# TREM_STM_DAUGHTERBOARD.net
KiCad netlist of a schematic drawn in EAGLE
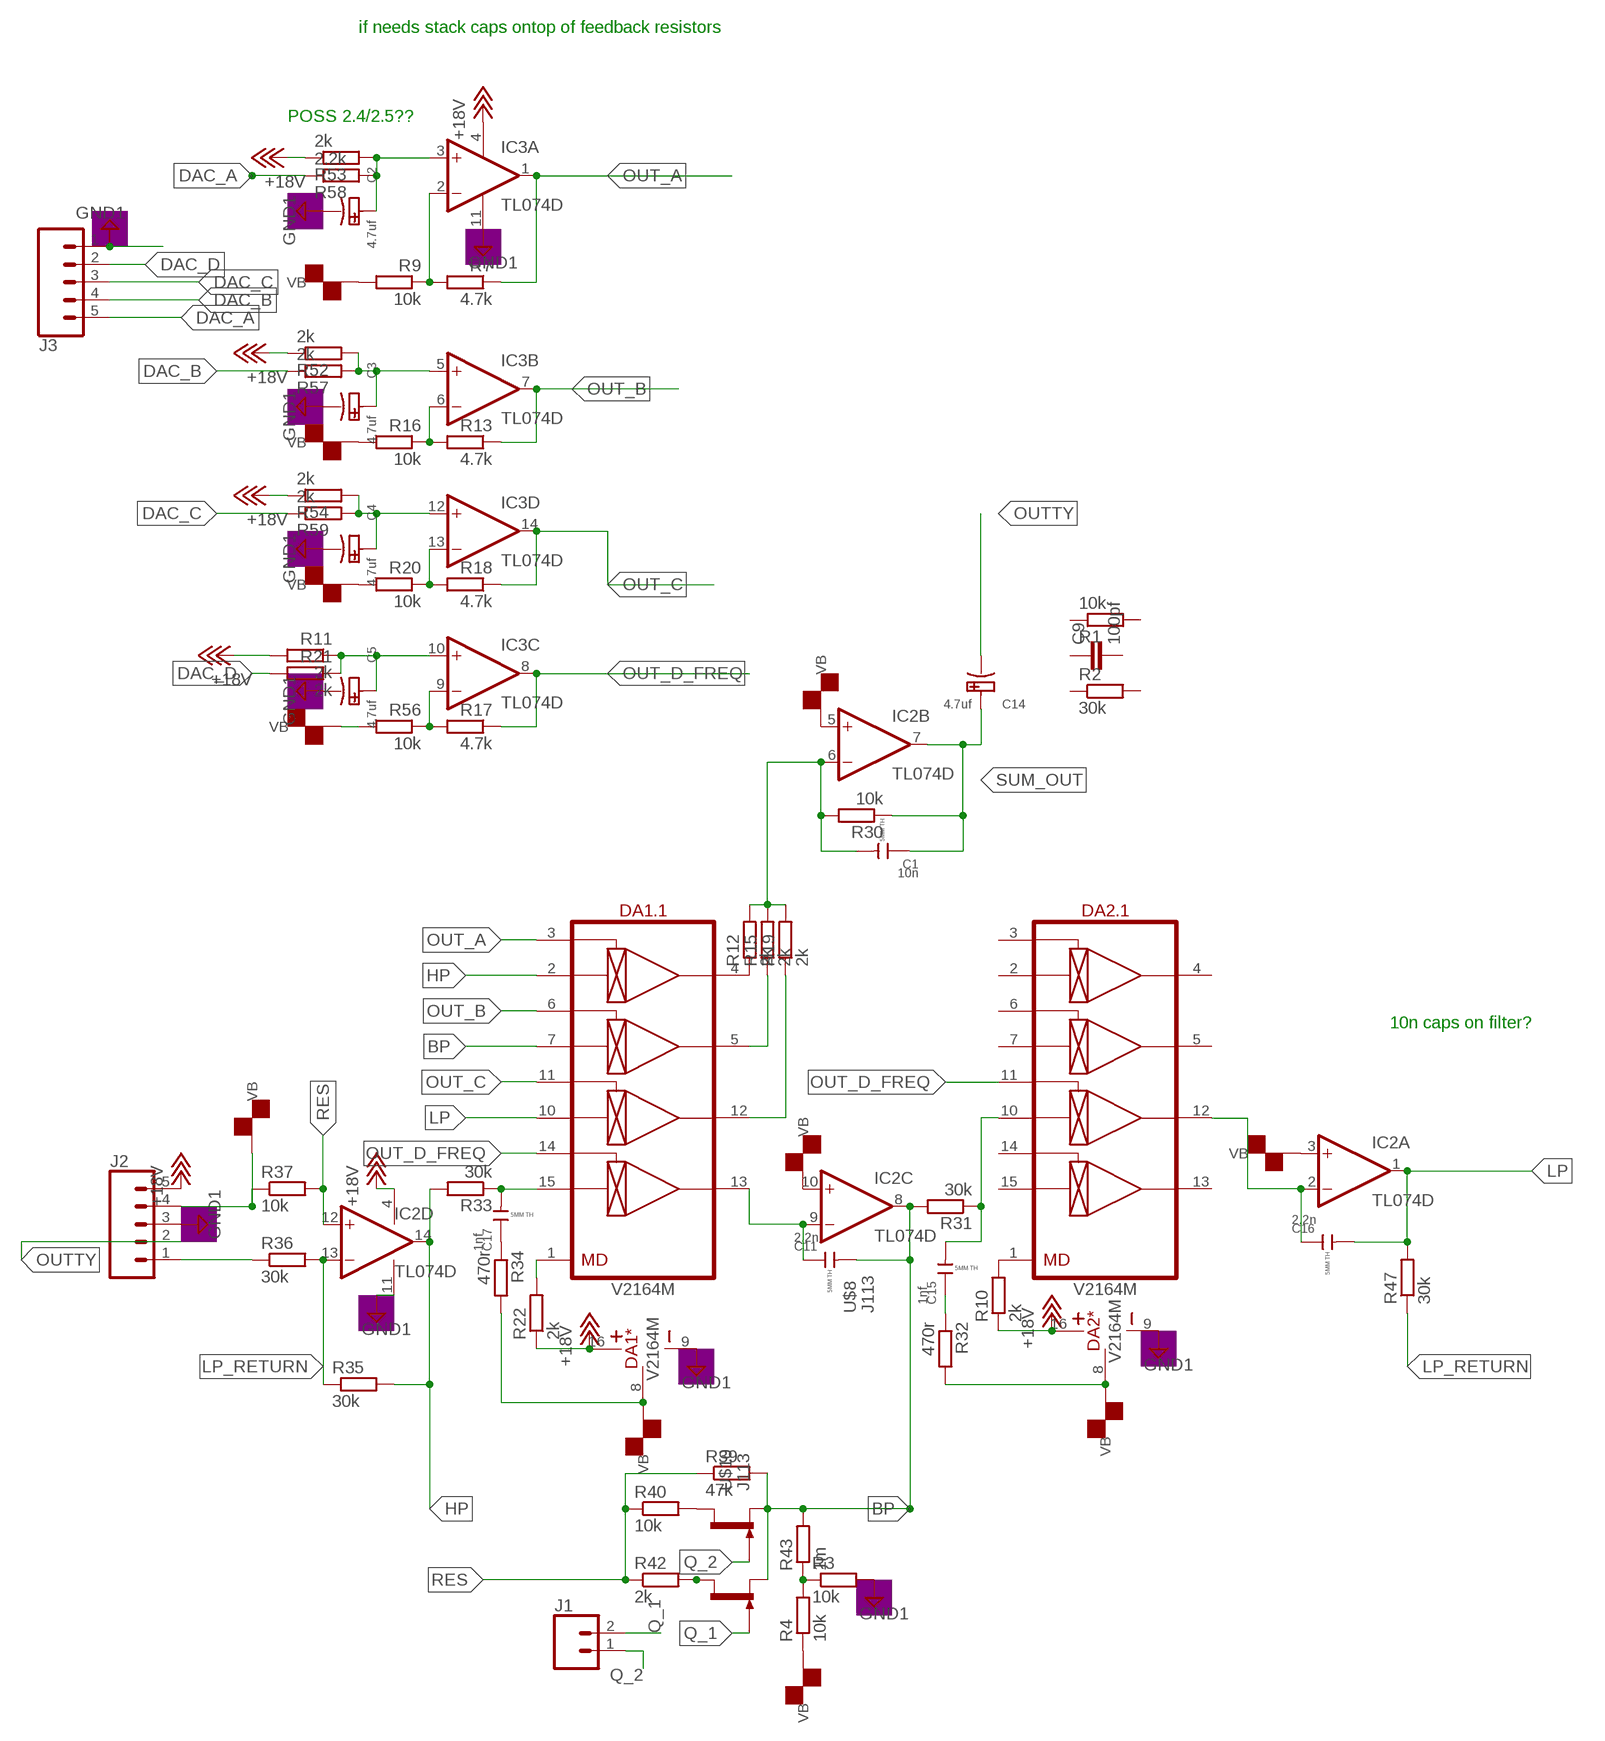
[diagram p0: schematic, sheet 1]

(export (version "E")
  (design (tool "Eeschema 10.0.6"))
  (components
    (comp (ref "C1")
      (value "10n")
      (footprint "eagle-import:CERAMIC-5MM")
      (fields (field (name "PACKAGE") "5MM TH"))
      (libsource (lib "eagle-import") (part "THRU_HOLE_5MM_SPACING"))
    )
    (comp (ref "C2")
      (value "4.7uf")
      (footprint "eagle-import:PC-D5.3MM")
      (libsource (lib "eagle-import") (part "THRU-HOLE-POLARIZED"))
    )
    (comp (ref "C3")
      (value "4.7uf")
      (footprint "eagle-import:PC-D5.3MM")
      (libsource (lib "eagle-import") (part "THRU-HOLE-POLARIZED"))
    )
    (comp (ref "C4")
      (value "4.7uf")
      (footprint "eagle-import:PC-D5.3MM")
      (libsource (lib "eagle-import") (part "THRU-HOLE-POLARIZED"))
    )
    (comp (ref "C5")
      (value "4.7uf")
      (footprint "eagle-import:PC-D5.3MM")
      (libsource (lib "eagle-import") (part "THRU-HOLE-POLARIZED"))
    )
    (comp (ref "C9")
      (value "100pf")
      (footprint "eagle-import:C1206")
      (libsource (lib "eagle-import") (part "C-EUC1206"))
    )
    (comp (ref "C11")
      (value "2.2n")
      (footprint "eagle-import:CERAMIC-5MM")
      (fields (field (name "PACKAGE") "5MM TH"))
      (libsource (lib "eagle-import") (part "THRU_HOLE_5MM_SPACING"))
    )
    (comp (ref "C14")
      (value "4.7uf")
      (footprint "eagle-import:PC-D5.3MM")
      (libsource (lib "eagle-import") (part "THRU-HOLE-POLARIZED"))
    )
    (comp (ref "C15")
      (value "1nf")
      (footprint "eagle-import:CERAMIC-5MM")
      (fields (field (name "PACKAGE") "5MM TH"))
      (libsource (lib "eagle-import") (part "THRU_HOLE_5MM_SPACING"))
    )
    (comp (ref "C16")
      (value "2.2n")
      (footprint "eagle-import:CERAMIC-5MM")
      (fields (field (name "PACKAGE") "5MM TH"))
      (libsource (lib "eagle-import") (part "THRU_HOLE_5MM_SPACING"))
    )
    (comp (ref "C17")
      (value "1nf")
      (footprint "eagle-import:CERAMIC-5MM")
      (fields (field (name "PACKAGE") "5MM TH"))
      (libsource (lib "eagle-import") (part "THRU_HOLE_5MM_SPACING"))
    )
    (comp (ref "DA1")
      (value "V2164M")
      (footprint "eagle-import:SO-16")
      (libsource (lib "eagle-import") (part "V2164M"))
    )
    (comp (ref "DA2")
      (value "V2164M")
      (footprint "eagle-import:SO-16")
      (libsource (lib "eagle-import") (part "V2164M"))
    )
    (comp (ref "IC2")
      (value "TL074D")
      (footprint "eagle-import:SO14")
      (libsource (lib "eagle-import") (part "TL074D"))
    )
    (comp (ref "IC3")
      (value "TL074D")
      (footprint "eagle-import:SO14")
      (libsource (lib "eagle-import") (part "TL074D"))
    )
    (comp (ref "J1")
      (value "CONN_02PTH3")
      (footprint "eagle-import:1X02_LONGPADS")
      (libsource (lib "eagle-import") (part "CONN_02PTH3"))
    )
    (comp (ref "J2")
      (value "CONN_05PTH_LONGPADS")
      (footprint "eagle-import:1X05_LONGPADS")
      (libsource (lib "eagle-import") (part "CONN_05PTH_LONGPADS"))
    )
    (comp (ref "J3")
      (value "CONN_05PTH_LONGPADS")
      (footprint "eagle-import:1X05_LONGPADS")
      (libsource (lib "eagle-import") (part "CONN_05PTH_LONGPADS"))
    )
    (comp (ref "R1")
      (value "10k")
      (footprint "eagle-import:M1206")
      (libsource (lib "eagle-import") (part "R-EU_M1206"))
    )
    (comp (ref "R2")
      (value "30k")
      (footprint "eagle-import:M1206")
      (libsource (lib "eagle-import") (part "R-EU_M1206"))
    )
    (comp (ref "R3")
      (value "10k")
      (footprint "eagle-import:M1206")
      (libsource (lib "eagle-import") (part "R-EU_M1206"))
    )
    (comp (ref "R4")
      (value "10k")
      (footprint "eagle-import:M1206")
      (libsource (lib "eagle-import") (part "R-EU_M1206"))
    )
    (comp (ref "R7")
      (value "4.7k")
      (footprint "eagle-import:M1206")
      (libsource (lib "eagle-import") (part "R-EU_M1206"))
    )
    (comp (ref "R9")
      (value "10k")
      (footprint "eagle-import:M1206")
      (libsource (lib "eagle-import") (part "R-EU_M1206"))
    )
    (comp (ref "R10")
      (value "2k")
      (footprint "eagle-import:M1206")
      (libsource (lib "eagle-import") (part "R-EU_M1206"))
    )
    (comp (ref "R11")
      (value "2k")
      (footprint "eagle-import:M1206")
      (libsource (lib "eagle-import") (part "R-EU_M1206"))
    )
    (comp (ref "R12")
      (value "2k")
      (footprint "eagle-import:M1206")
      (libsource (lib "eagle-import") (part "R-EU_M1206"))
    )
    (comp (ref "R13")
      (value "4.7k")
      (footprint "eagle-import:M1206")
      (libsource (lib "eagle-import") (part "R-EU_M1206"))
    )
    (comp (ref "R15")
      (value "2k")
      (footprint "eagle-import:M1206")
      (libsource (lib "eagle-import") (part "R-EU_M1206"))
    )
    (comp (ref "R16")
      (value "10k")
      (footprint "eagle-import:M1206")
      (libsource (lib "eagle-import") (part "R-EU_M1206"))
    )
    (comp (ref "R17")
      (value "4.7k")
      (footprint "eagle-import:M1206")
      (libsource (lib "eagle-import") (part "R-EU_M1206"))
    )
    (comp (ref "R18")
      (value "4.7k")
      (footprint "eagle-import:M1206")
      (libsource (lib "eagle-import") (part "R-EU_M1206"))
    )
    (comp (ref "R19")
      (value "2k")
      (footprint "eagle-import:M1206")
      (libsource (lib "eagle-import") (part "R-EU_M1206"))
    )
    (comp (ref "R20")
      (value "10k")
      (footprint "eagle-import:M1206")
      (libsource (lib "eagle-import") (part "R-EU_M1206"))
    )
    (comp (ref "R21")
      (value "2k")
      (footprint "eagle-import:M1206")
      (libsource (lib "eagle-import") (part "R-EU_M1206"))
    )
    (comp (ref "R22")
      (value "2k")
      (footprint "eagle-import:M1206")
      (libsource (lib "eagle-import") (part "R-EU_M1206"))
    )
    (comp (ref "R30")
      (value "10k")
      (footprint "eagle-import:M1206")
      (libsource (lib "eagle-import") (part "R-EU_M1206"))
    )
    (comp (ref "R31")
      (value "30k")
      (footprint "eagle-import:M1206")
      (libsource (lib "eagle-import") (part "R-EU_M1206"))
    )
    (comp (ref "R32")
      (value "470r")
      (footprint "eagle-import:M1206")
      (libsource (lib "eagle-import") (part "R-EU_M1206"))
    )
    (comp (ref "R33")
      (value "30k")
      (footprint "eagle-import:M1206")
      (libsource (lib "eagle-import") (part "R-EU_M1206"))
    )
    (comp (ref "R34")
      (value "470r")
      (footprint "eagle-import:M1206")
      (libsource (lib "eagle-import") (part "R-EU_M1206"))
    )
    (comp (ref "R35")
      (value "30k")
      (footprint "eagle-import:M1206")
      (libsource (lib "eagle-import") (part "R-EU_M1206"))
    )
    (comp (ref "R36")
      (value "30k")
      (footprint "eagle-import:M1206")
      (libsource (lib "eagle-import") (part "R-EU_M1206"))
    )
    (comp (ref "R37")
      (value "10k")
      (footprint "eagle-import:M1206")
      (libsource (lib "eagle-import") (part "R-EU_M1206"))
    )
    (comp (ref "R39")
      (value "47k")
      (footprint "eagle-import:M1206")
      (libsource (lib "eagle-import") (part "R-EU_M1206"))
    )
    (comp (ref "R40")
      (value "10k")
      (footprint "eagle-import:M1206")
      (libsource (lib "eagle-import") (part "R-EU_M1206"))
    )
    (comp (ref "R42")
      (value "2k")
      (footprint "eagle-import:M1206")
      (libsource (lib "eagle-import") (part "R-EU_M1206"))
    )
    (comp (ref "R43")
      (value "1m")
      (footprint "eagle-import:M1206")
      (libsource (lib "eagle-import") (part "R-EU_M1206"))
    )
    (comp (ref "R47")
      (value "30k")
      (footprint "eagle-import:M1206")
      (libsource (lib "eagle-import") (part "R-EU_M1206"))
    )
    (comp (ref "R52")
      (value "2k")
      (footprint "eagle-import:M1206")
      (libsource (lib "eagle-import") (part "R-EU_M1206"))
    )
    (comp (ref "R53")
      (value "2k")
      (footprint "eagle-import:M1206")
      (libsource (lib "eagle-import") (part "R-EU_M1206"))
    )
    (comp (ref "R54")
      (value "2k")
      (footprint "eagle-import:M1206")
      (libsource (lib "eagle-import") (part "R-EU_M1206"))
    )
    (comp (ref "R56")
      (value "10k")
      (footprint "eagle-import:M1206")
      (libsource (lib "eagle-import") (part "R-EU_M1206"))
    )
    (comp (ref "R57")
      (value "2k")
      (footprint "eagle-import:M1206")
      (libsource (lib "eagle-import") (part "R-EU_M1206"))
    )
    (comp (ref "R58")
      (value "2.2k")
      (footprint "eagle-import:M1206")
      (libsource (lib "eagle-import") (part "R-EU_M1206"))
    )
    (comp (ref "R59")
      (value "2k")
      (footprint "eagle-import:M1206")
      (libsource (lib "eagle-import") (part "R-EU_M1206"))
    )
    (comp (ref "U$8")
      (value "J113")
      (footprint "eagle-import:TO92-")
      (libsource (lib "eagle-import") (part "J111"))
    )
    (comp (ref "U$10")
      (value "J113")
      (footprint "eagle-import:TO92-")
      (libsource (lib "eagle-import") (part "J111"))
    )
  )
  (nets
    (net (code "1") (name "+18V") (class "Default")
      (node (ref "DA1") (pin "16") (pinfunction "V+_16") (pintype "power_in"))
      (node (ref "DA2") (pin "16") (pinfunction "V+_16") (pintype "power_in"))
      (node (ref "IC2") (pin "4") (pinfunction "V+_4") (pintype "power_in"))
      (node (ref "IC3") (pin "4") (pinfunction "V+_4") (pintype "power_in"))
      (node (ref "J2") (pin "5") (pinfunction "5_5") (pintype "passive"))
      (node (ref "R10") (pin "1") (pinfunction "1_1") (pintype "passive"))
      (node (ref "R11") (pin "2") (pinfunction "2_2") (pintype "passive"))
      (node (ref "R22") (pin "1") (pinfunction "1_1") (pintype "passive"))
      (node (ref "R52") (pin "1") (pinfunction "1_1") (pintype "passive"))
      (node (ref "R53") (pin "1") (pinfunction "1_1") (pintype "passive"))
      (node (ref "R54") (pin "1") (pinfunction "1_1") (pintype "passive"))
    )
    (net (code "2") (name "BP") (class "Default")
      (node (ref "C11") (pin "2") (pinfunction "2_2") (pintype "passive"))
      (node (ref "DA1") (pin "7") (pinfunction "IN2_7") (pintype "input"))
      (node (ref "IC2") (pin "8") (pinfunction "OUT_8") (pintype "output"))
      (node (ref "R31") (pin "2") (pinfunction "2_2") (pintype "passive"))
      (node (ref "R39") (pin "2") (pinfunction "2_2") (pintype "passive"))
      (node (ref "R43") (pin "2") (pinfunction "2_2") (pintype "passive"))
      (node (ref "U$10") (pin "2") (pinfunction "S_2") (pintype "passive"))
      (node (ref "U$8") (pin "2") (pinfunction "S_2") (pintype "passive"))
    )
    (net (code "3") (name "DAC_A") (class "Default")
      (node (ref "J3") (pin "5") (pinfunction "5_5") (pintype "passive"))
      (node (ref "R58") (pin "1") (pinfunction "1_1") (pintype "passive"))
    )
    (net (code "4") (name "DAC_B") (class "Default")
      (node (ref "J3") (pin "4") (pinfunction "4_4") (pintype "passive"))
      (node (ref "R57") (pin "1") (pinfunction "1_1") (pintype "passive"))
    )
    (net (code "5") (name "DAC_C") (class "Default")
      (node (ref "J3") (pin "3") (pinfunction "3_3") (pintype "passive"))
      (node (ref "R59") (pin "1") (pinfunction "1_1") (pintype "passive"))
    )
    (net (code "6") (name "DAC_D") (class "Default")
      (node (ref "J3") (pin "2") (pinfunction "2_2") (pintype "passive"))
      (node (ref "R21") (pin "2") (pinfunction "2_2") (pintype "passive"))
    )
    (net (code "7") (name "GND1") (class "Default")
      (node (ref "C2") (pin "-") (pinfunction "-_-") (pintype "passive"))
      (node (ref "C3") (pin "-") (pinfunction "-_-") (pintype "passive"))
      (node (ref "C4") (pin "-") (pinfunction "-_-") (pintype "passive"))
      (node (ref "C5") (pin "-") (pinfunction "-_-") (pintype "passive"))
      (node (ref "DA1") (pin "9") (pinfunction "V-_9") (pintype "power_in"))
      (node (ref "DA2") (pin "9") (pinfunction "V-_9") (pintype "power_in"))
      (node (ref "IC2") (pin "11") (pinfunction "V-_11") (pintype "power_in"))
      (node (ref "IC3") (pin "11") (pinfunction "V-_11") (pintype "power_in"))
      (node (ref "J2") (pin "3") (pinfunction "3_3") (pintype "passive"))
      (node (ref "J3") (pin "1") (pinfunction "1_1") (pintype "passive"))
      (node (ref "R3") (pin "2") (pinfunction "2_2") (pintype "passive"))
    )
    (net (code "8") (name "HP") (class "Default")
      (node (ref "DA1") (pin "2") (pinfunction "IN1_2") (pintype "input"))
      (node (ref "IC2") (pin "14") (pinfunction "OUT_14") (pintype "output"))
      (node (ref "R33") (pin "2") (pinfunction "2_2") (pintype "passive"))
      (node (ref "R35") (pin "2") (pinfunction "2_2") (pintype "passive"))
    )
    (net (code "9") (name "LP") (class "Default")
      (node (ref "C16") (pin "2") (pinfunction "2_2") (pintype "passive"))
      (node (ref "DA1") (pin "10") (pinfunction "IN3_10") (pintype "input"))
      (node (ref "IC2") (pin "1") (pinfunction "OUT_1") (pintype "output"))
      (node (ref "R47") (pin "2") (pinfunction "2_2") (pintype "passive"))
    )
    (net (code "10") (name "LP_RETURN") (class "Default")
      (node (ref "IC2") (pin "13") (pinfunction "-IN_13") (pintype "input"))
      (node (ref "R35") (pin "1") (pinfunction "1_1") (pintype "passive"))
      (node (ref "R36") (pin "2") (pinfunction "2_2") (pintype "passive"))
      (node (ref "R47") (pin "1") (pinfunction "1_1") (pintype "passive"))
    )
    (net (code "11") (name "Net-(C15-Pad1)") (class "Default")
      (node (ref "C15") (pin "1") (pinfunction "1_1") (pintype "passive"))
      (node (ref "R32") (pin "1") (pinfunction "1_1") (pintype "passive"))
    )
    (net (code "12") (name "Net-(C17-Pad1)") (class "Default")
      (node (ref "C17") (pin "1") (pinfunction "1_1") (pintype "passive"))
      (node (ref "R34") (pin "1") (pinfunction "1_1") (pintype "passive"))
    )
    (net (code "13") (name "Net-(DA1B-IN4)") (class "Default")
      (node (ref "C17") (pin "2") (pinfunction "2_2") (pintype "passive"))
      (node (ref "DA1") (pin "15") (pinfunction "IN4_15") (pintype "input"))
      (node (ref "R33") (pin "1") (pinfunction "1_1") (pintype "passive"))
    )
    (net (code "14") (name "Net-(DA1B-MD)") (class "Default")
      (node (ref "DA1") (pin "1") (pinfunction "MD_1") (pintype "output"))
      (node (ref "R22") (pin "2") (pinfunction "2_2") (pintype "passive"))
    )
    (net (code "15") (name "Net-(DA1B-OUT1)") (class "Default")
      (node (ref "DA1") (pin "4") (pinfunction "OUT1_4") (pintype "output"))
      (node (ref "R12") (pin "1") (pinfunction "1_1") (pintype "passive"))
    )
    (net (code "16") (name "Net-(DA1B-OUT2)") (class "Default")
      (node (ref "DA1") (pin "5") (pinfunction "OUT2_5") (pintype "output"))
      (node (ref "R15") (pin "1") (pinfunction "1_1") (pintype "passive"))
    )
    (net (code "17") (name "Net-(DA1B-OUT3)") (class "Default")
      (node (ref "DA1") (pin "12") (pinfunction "OUT3_12") (pintype "output"))
      (node (ref "R19") (pin "1") (pinfunction "1_1") (pintype "passive"))
    )
    (net (code "18") (name "Net-(DA1B-OUT4)") (class "Default")
      (node (ref "C11") (pin "1") (pinfunction "1_1") (pintype "passive"))
      (node (ref "DA1") (pin "13") (pinfunction "OUT4_13") (pintype "output"))
      (node (ref "IC2") (pin "9") (pinfunction "-IN_9") (pintype "input"))
    )
    (net (code "19") (name "Net-(DA2B-IN3)") (class "Default")
      (node (ref "C15") (pin "2") (pinfunction "2_2") (pintype "passive"))
      (node (ref "DA2") (pin "10") (pinfunction "IN3_10") (pintype "input"))
      (node (ref "R31") (pin "1") (pinfunction "1_1") (pintype "passive"))
    )
    (net (code "20") (name "Net-(DA2B-MD)") (class "Default")
      (node (ref "DA2") (pin "1") (pinfunction "MD_1") (pintype "output"))
      (node (ref "R10") (pin "2") (pinfunction "2_2") (pintype "passive"))
    )
    (net (code "21") (name "Net-(DA2B-OUT3)") (class "Default")
      (node (ref "C16") (pin "1") (pinfunction "1_1") (pintype "passive"))
      (node (ref "DA2") (pin "12") (pinfunction "OUT3_12") (pintype "output"))
      (node (ref "IC2") (pin "2") (pinfunction "-IN_2") (pintype "input"))
    )
    (net (code "22") (name "Net-(IC2B--IN)") (class "Default")
      (node (ref "C1") (pin "2") (pinfunction "2_2") (pintype "passive"))
      (node (ref "IC2") (pin "6") (pinfunction "-IN_6") (pintype "input"))
      (node (ref "R12") (pin "2") (pinfunction "2_2") (pintype "passive"))
      (node (ref "R15") (pin "2") (pinfunction "2_2") (pintype "passive"))
      (node (ref "R19") (pin "2") (pinfunction "2_2") (pintype "passive"))
      (node (ref "R30") (pin "2") (pinfunction "2_2") (pintype "passive"))
    )
    (net (code "23") (name "Net-(IC3A-+IN)") (class "Default")
      (node (ref "C2") (pin "+") (pinfunction "+_+") (pintype "passive"))
      (node (ref "IC3") (pin "3") (pinfunction "+IN_3") (pintype "input"))
      (node (ref "R53") (pin "2") (pinfunction "2_2") (pintype "passive"))
      (node (ref "R58") (pin "2") (pinfunction "2_2") (pintype "passive"))
    )
    (net (code "24") (name "Net-(IC3A--IN)") (class "Default")
      (node (ref "IC3") (pin "2") (pinfunction "-IN_2") (pintype "input"))
      (node (ref "R7") (pin "2") (pinfunction "2_2") (pintype "passive"))
      (node (ref "R9") (pin "1") (pinfunction "1_1") (pintype "passive"))
    )
    (net (code "25") (name "Net-(IC3B-+IN)") (class "Default")
      (node (ref "C3") (pin "+") (pinfunction "+_+") (pintype "passive"))
      (node (ref "IC3") (pin "5") (pinfunction "+IN_5") (pintype "input"))
      (node (ref "R52") (pin "2") (pinfunction "2_2") (pintype "passive"))
      (node (ref "R57") (pin "2") (pinfunction "2_2") (pintype "passive"))
    )
    (net (code "26") (name "Net-(IC3B--IN)") (class "Default")
      (node (ref "IC3") (pin "6") (pinfunction "-IN_6") (pintype "input"))
      (node (ref "R13") (pin "2") (pinfunction "2_2") (pintype "passive"))
      (node (ref "R16") (pin "1") (pinfunction "1_1") (pintype "passive"))
    )
    (net (code "27") (name "Net-(IC3C-+IN)") (class "Default")
      (node (ref "C5") (pin "+") (pinfunction "+_+") (pintype "passive"))
      (node (ref "IC3") (pin "10") (pinfunction "+IN_10") (pintype "input"))
      (node (ref "R11") (pin "1") (pinfunction "1_1") (pintype "passive"))
      (node (ref "R21") (pin "1") (pinfunction "1_1") (pintype "passive"))
    )
    (net (code "28") (name "Net-(IC3C--IN)") (class "Default")
      (node (ref "IC3") (pin "9") (pinfunction "-IN_9") (pintype "input"))
      (node (ref "R17") (pin "2") (pinfunction "2_2") (pintype "passive"))
      (node (ref "R56") (pin "1") (pinfunction "1_1") (pintype "passive"))
    )
    (net (code "29") (name "Net-(IC3D-+IN)") (class "Default")
      (node (ref "C4") (pin "+") (pinfunction "+_+") (pintype "passive"))
      (node (ref "IC3") (pin "12") (pinfunction "+IN_12") (pintype "input"))
      (node (ref "R54") (pin "2") (pinfunction "2_2") (pintype "passive"))
      (node (ref "R59") (pin "2") (pinfunction "2_2") (pintype "passive"))
    )
    (net (code "30") (name "Net-(IC3D--IN)") (class "Default")
      (node (ref "IC3") (pin "13") (pinfunction "-IN_13") (pintype "input"))
      (node (ref "R18") (pin "2") (pinfunction "2_2") (pintype "passive"))
      (node (ref "R20") (pin "1") (pinfunction "1_1") (pintype "passive"))
    )
    (net (code "31") (name "Net-(J2-Pad1)") (class "Default")
      (node (ref "J2") (pin "1") (pinfunction "1_1") (pintype "passive"))
      (node (ref "R36") (pin "1") (pinfunction "1_1") (pintype "passive"))
    )
    (net (code "32") (name "Net-(R3-Pad1)") (class "Default")
      (node (ref "R3") (pin "1") (pinfunction "1_1") (pintype "passive"))
      (node (ref "R4") (pin "2") (pinfunction "2_2") (pintype "passive"))
      (node (ref "R43") (pin "1") (pinfunction "1_1") (pintype "passive"))
    )
    (net (code "33") (name "Net-(U$8-D)") (class "Default")
      (node (ref "R42") (pin "2") (pinfunction "2_2") (pintype "passive"))
      (node (ref "U$8") (pin "3") (pinfunction "D_3") (pintype "passive"))
    )
    (net (code "34") (name "Net-(U$10-D)") (class "Default")
      (node (ref "R40") (pin "2") (pinfunction "2_2") (pintype "passive"))
      (node (ref "U$10") (pin "3") (pinfunction "D_3") (pintype "passive"))
    )
    (net (code "35") (name "OUTTY") (class "Default")
      (node (ref "C14") (pin "-") (pinfunction "-_-") (pintype "passive"))
      (node (ref "J2") (pin "2") (pinfunction "2_2") (pintype "passive"))
    )
    (net (code "36") (name "OUT_A") (class "Default")
      (node (ref "DA1") (pin "3") (pinfunction "CV1_3") (pintype "input"))
      (node (ref "IC3") (pin "1") (pinfunction "OUT_1") (pintype "output"))
      (node (ref "R7") (pin "1") (pinfunction "1_1") (pintype "passive"))
    )
    (net (code "37") (name "OUT_B") (class "Default")
      (node (ref "DA1") (pin "6") (pinfunction "CV2_6") (pintype "input"))
      (node (ref "IC3") (pin "7") (pinfunction "OUT_7") (pintype "output"))
      (node (ref "R13") (pin "1") (pinfunction "1_1") (pintype "passive"))
    )
    (net (code "38") (name "OUT_C") (class "Default")
      (node (ref "DA1") (pin "11") (pinfunction "CV3_11") (pintype "input"))
      (node (ref "IC3") (pin "14") (pinfunction "OUT_14") (pintype "output"))
      (node (ref "R18") (pin "1") (pinfunction "1_1") (pintype "passive"))
    )
    (net (code "39") (name "OUT_D_FREQ") (class "Default")
      (node (ref "DA1") (pin "14") (pinfunction "CV4_14") (pintype "input"))
      (node (ref "DA2") (pin "11") (pinfunction "CV3_11") (pintype "input"))
      (node (ref "IC3") (pin "8") (pinfunction "OUT_8") (pintype "output"))
      (node (ref "R17") (pin "1") (pinfunction "1_1") (pintype "passive"))
    )
    (net (code "40") (name "Q_1") (class "Default")
      (node (ref "J1") (pin "2") (pinfunction "2_2") (pintype "passive"))
      (node (ref "U$8") (pin "1") (pinfunction "G_1") (pintype "passive"))
    )
    (net (code "41") (name "Q_2") (class "Default")
      (node (ref "J1") (pin "1") (pinfunction "1_1") (pintype "passive"))
      (node (ref "U$10") (pin "1") (pinfunction "G_1") (pintype "passive"))
    )
    (net (code "42") (name "RES") (class "Default")
      (node (ref "IC2") (pin "12") (pinfunction "+IN_12") (pintype "input"))
      (node (ref "R37") (pin "2") (pinfunction "2_2") (pintype "passive"))
      (node (ref "R39") (pin "1") (pinfunction "1_1") (pintype "passive"))
      (node (ref "R40") (pin "1") (pinfunction "1_1") (pintype "passive"))
      (node (ref "R42") (pin "1") (pinfunction "1_1") (pintype "passive"))
    )
    (net (code "43") (name "SUM_OUT") (class "Default")
      (node (ref "C1") (pin "1") (pinfunction "1_1") (pintype "passive"))
      (node (ref "C14") (pin "+") (pinfunction "+_+") (pintype "passive"))
      (node (ref "IC2") (pin "7") (pinfunction "OUT_7") (pintype "output"))
      (node (ref "R30") (pin "1") (pinfunction "1_1") (pintype "passive"))
    )
    (net (code "44") (name "VB") (class "Default")
      (node (ref "DA1") (pin "8") (pinfunction "GND_8") (pintype "power_in"))
      (node (ref "DA2") (pin "8") (pinfunction "GND_8") (pintype "power_in"))
      (node (ref "IC2") (pin "10") (pinfunction "+IN_10") (pintype "input"))
      (node (ref "IC2") (pin "3") (pinfunction "+IN_3") (pintype "input"))
      (node (ref "IC2") (pin "5") (pinfunction "+IN_5") (pintype "input"))
      (node (ref "J2") (pin "4") (pinfunction "4_4") (pintype "passive"))
      (node (ref "R16") (pin "2") (pinfunction "2_2") (pintype "passive"))
      (node (ref "R20") (pin "2") (pinfunction "2_2") (pintype "passive"))
      (node (ref "R32") (pin "2") (pinfunction "2_2") (pintype "passive"))
      (node (ref "R34") (pin "2") (pinfunction "2_2") (pintype "passive"))
      (node (ref "R37") (pin "1") (pinfunction "1_1") (pintype "passive"))
      (node (ref "R4") (pin "1") (pinfunction "1_1") (pintype "passive"))
      (node (ref "R56") (pin "2") (pinfunction "2_2") (pintype "passive"))
      (node (ref "R9") (pin "2") (pinfunction "2_2") (pintype "passive"))
    )
    (net (code "45") (name "unconnected-(C9-Pad1)") (class "Default")
      (node (ref "C9") (pin "1") (pinfunction "1_1") (pintype "passive"))
    )
    (net (code "46") (name "unconnected-(C9-Pad2)") (class "Default")
      (node (ref "C9") (pin "2") (pinfunction "2_2") (pintype "passive"))
    )
    (net (code "47") (name "unconnected-(DA2B-CV1-Pad3)") (class "Default")
      (node (ref "DA2") (pin "3") (pinfunction "CV1_3") (pintype "input"))
    )
    (net (code "48") (name "unconnected-(DA2B-CV2-Pad6)") (class "Default")
      (node (ref "DA2") (pin "6") (pinfunction "CV2_6") (pintype "input"))
    )
    (net (code "49") (name "unconnected-(DA2B-CV4-Pad14)") (class "Default")
      (node (ref "DA2") (pin "14") (pinfunction "CV4_14") (pintype "input"))
    )
    (net (code "50") (name "unconnected-(DA2B-IN1-Pad2)") (class "Default")
      (node (ref "DA2") (pin "2") (pinfunction "IN1_2") (pintype "input"))
    )
    (net (code "51") (name "unconnected-(DA2B-IN2-Pad7)") (class "Default")
      (node (ref "DA2") (pin "7") (pinfunction "IN2_7") (pintype "input"))
    )
    (net (code "52") (name "unconnected-(DA2B-IN4-Pad15)") (class "Default")
      (node (ref "DA2") (pin "15") (pinfunction "IN4_15") (pintype "input"))
    )
    (net (code "53") (name "unconnected-(DA2B-OUT1-Pad4)") (class "Default")
      (node (ref "DA2") (pin "4") (pinfunction "OUT1_4") (pintype "output"))
    )
    (net (code "54") (name "unconnected-(DA2B-OUT2-Pad5)") (class "Default")
      (node (ref "DA2") (pin "5") (pinfunction "OUT2_5") (pintype "output"))
    )
    (net (code "55") (name "unconnected-(DA2B-OUT4-Pad13)") (class "Default")
      (node (ref "DA2") (pin "13") (pinfunction "OUT4_13") (pintype "output"))
    )
    (net (code "56") (name "unconnected-(R1-Pad1)") (class "Default")
      (node (ref "R1") (pin "1") (pinfunction "1_1") (pintype "passive"))
    )
    (net (code "57") (name "unconnected-(R1-Pad2)") (class "Default")
      (node (ref "R1") (pin "2") (pinfunction "2_2") (pintype "passive"))
    )
    (net (code "58") (name "unconnected-(R2-Pad1)") (class "Default")
      (node (ref "R2") (pin "1") (pinfunction "1_1") (pintype "passive"))
    )
    (net (code "59") (name "unconnected-(R2-Pad2)") (class "Default")
      (node (ref "R2") (pin "2") (pinfunction "2_2") (pintype "passive"))
    )
  )
)
